# LED.net
KiCad netlist of a schematic drawn in Altium Designer
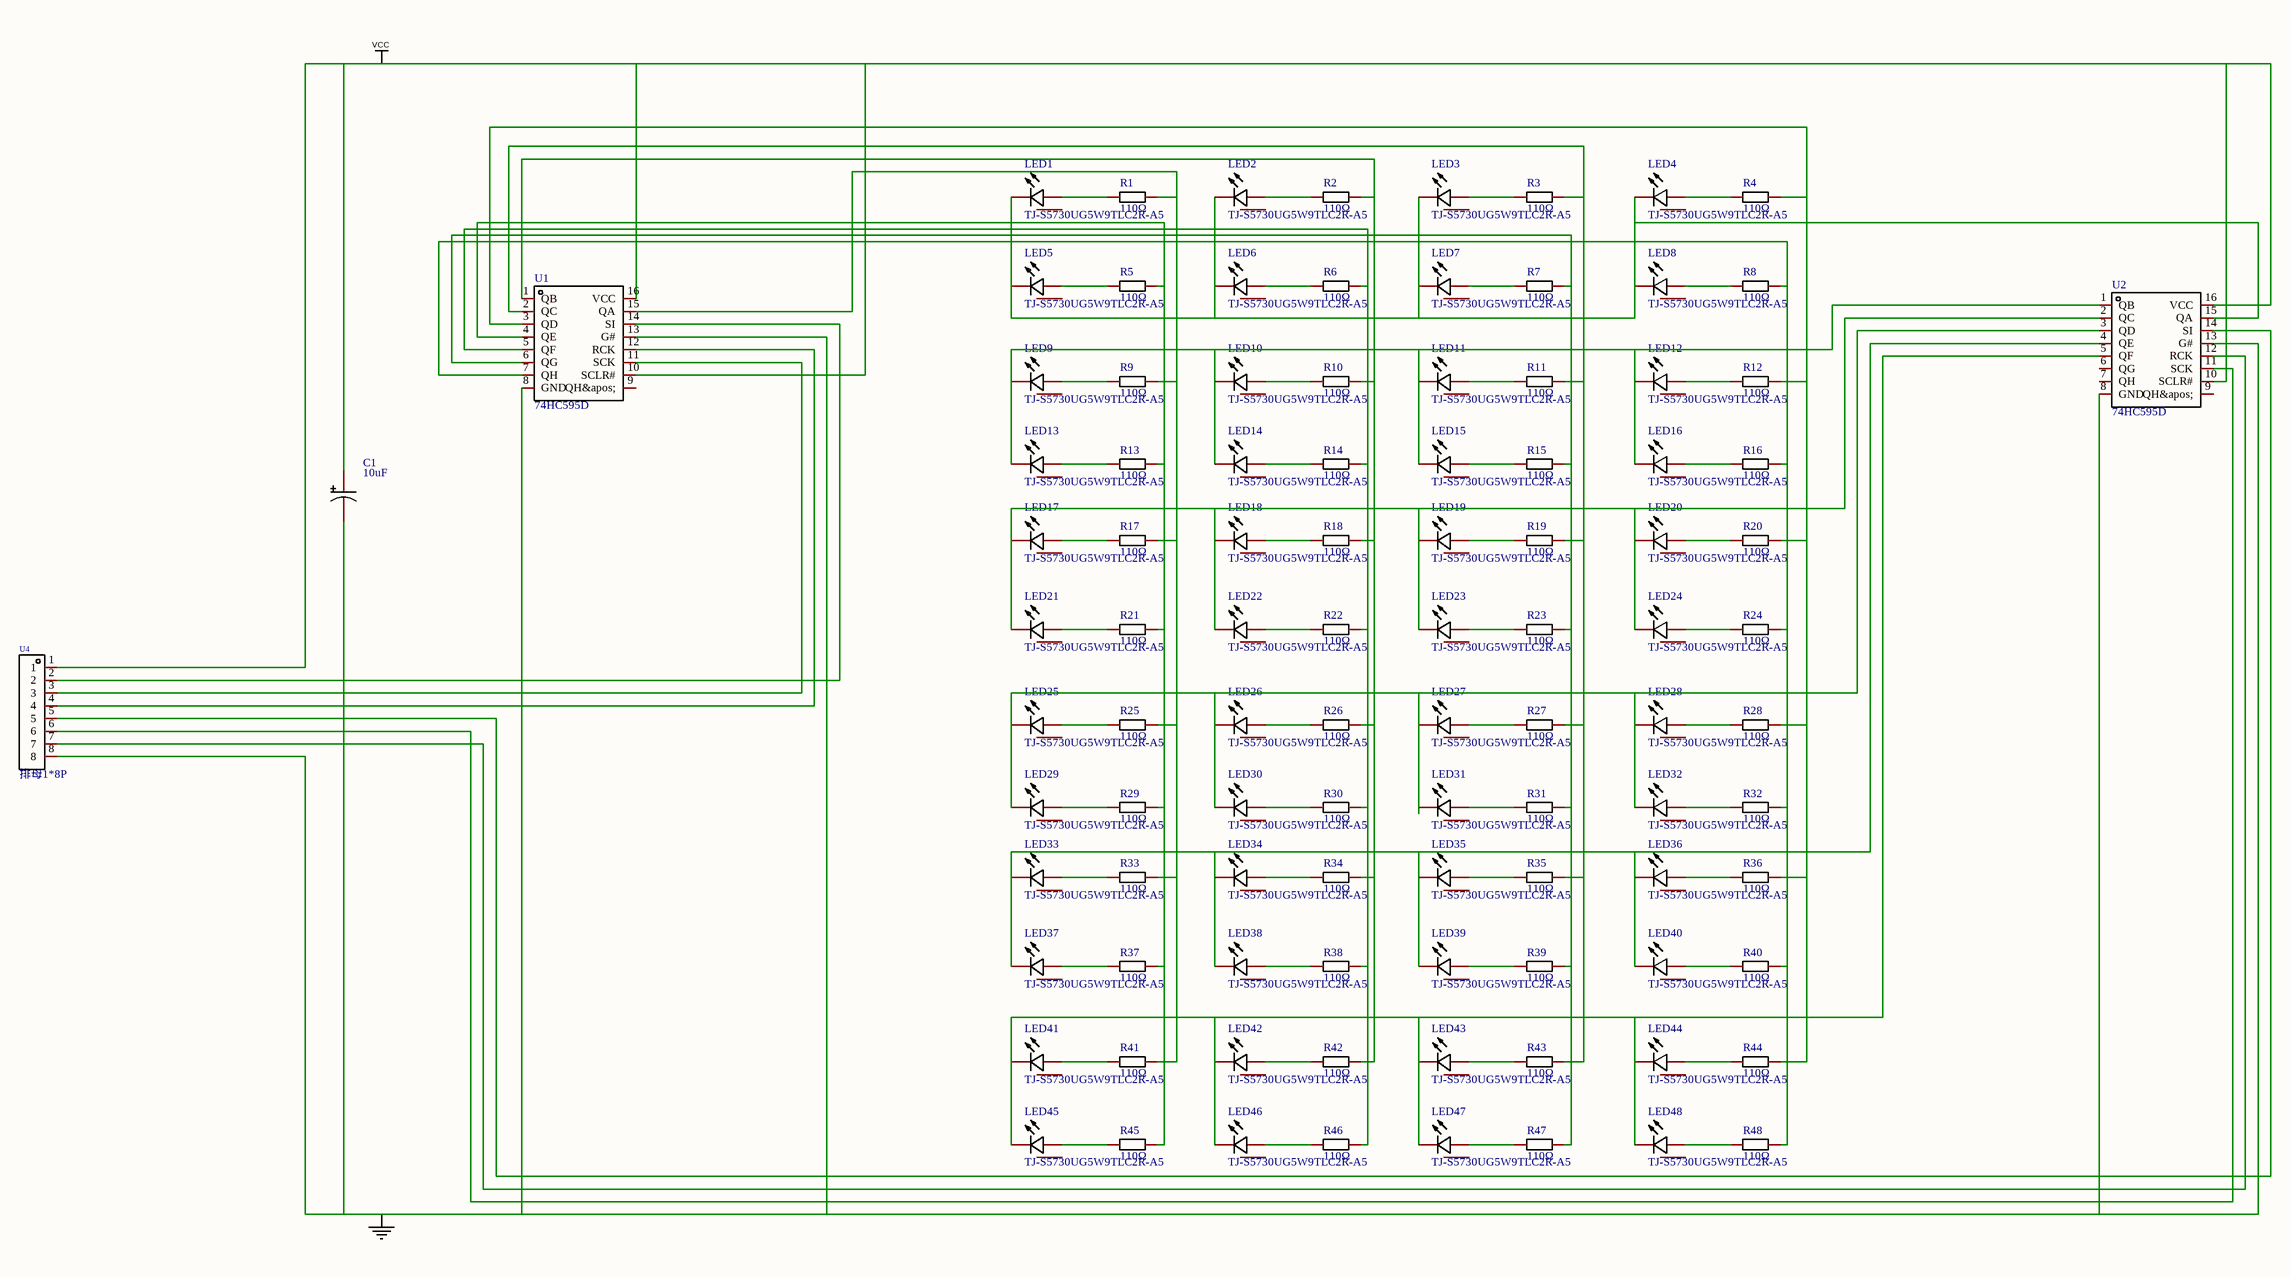
[diagram p0: LED.schdoc]

(export (version "E")
  (design (tool "Eeschema 10.0.6"))
  (components
    (comp (ref "C1")
      (value "10uF")
      (description "容值:10uF;精度:±20%;额定电压:50V;纹波电流:63.75mA@120Hz;等效串联电阻:-;")
      (fields
        (field (name "NAME") "10uF")
        (field (name "MANUFACTURER") "PANASONIC(松下)")
        (field (name "MANUFACTURER PART") "EEEFK1H100UR")
      )
      (libsource (lib "altium-import") (part "root_0_EEEFK1H100UR_"))
    )
    (comp (ref "LED1")
      (value "TJ-S5730UG5W9TLC2R-A5")
      (description "发光颜色:红灯;二极管配置:-;主波长:620nm~630nm;色温:-;功率:390mW;安装方式:-;")
      (fields (field (name "NAME") "TJ-S5730UG5W9TLC2R-A5") (field (name "MANUFACTURER") "TOGIALED(统佳)"))
      (libsource (lib "altium-import") (part "root_0_TJ-S5730UG5W9TLC2R-A5_"))
    )
    (comp (ref "LED2")
      (value "TJ-S5730UG5W9TLC2R-A5")
      (description "发光颜色:红灯;二极管配置:-;主波长:620nm~630nm;色温:-;功率:390mW;安装方式:-;")
      (fields (field (name "NAME") "TJ-S5730UG5W9TLC2R-A5") (field (name "MANUFACTURER") "TOGIALED(统佳)"))
      (libsource (lib "altium-import") (part "root_0_TJ-S5730UG5W9TLC2R-A5_"))
    )
    (comp (ref "LED3")
      (value "TJ-S5730UG5W9TLC2R-A5")
      (description "发光颜色:红灯;二极管配置:-;主波长:620nm~630nm;色温:-;功率:390mW;安装方式:-;")
      (fields (field (name "NAME") "TJ-S5730UG5W9TLC2R-A5") (field (name "MANUFACTURER") "TOGIALED(统佳)"))
      (libsource (lib "altium-import") (part "root_0_TJ-S5730UG5W9TLC2R-A5_"))
    )
    (comp (ref "LED4")
      (value "TJ-S5730UG5W9TLC2R-A5")
      (description "发光颜色:红灯;二极管配置:-;主波长:620nm~630nm;色温:-;功率:390mW;安装方式:-;")
      (fields (field (name "NAME") "TJ-S5730UG5W9TLC2R-A5") (field (name "MANUFACTURER") "TOGIALED(统佳)"))
      (libsource (lib "altium-import") (part "root_0_TJ-S5730UG5W9TLC2R-A5_"))
    )
    (comp (ref "LED5")
      (value "TJ-S5730UG5W9TLC2R-A5")
      (description "发光颜色:红灯;二极管配置:-;主波长:620nm~630nm;色温:-;功率:390mW;安装方式:-;")
      (fields (field (name "NAME") "TJ-S5730UG5W9TLC2R-A5") (field (name "MANUFACTURER") "TOGIALED(统佳)"))
      (libsource (lib "altium-import") (part "root_0_TJ-S5730UG5W9TLC2R-A5_"))
    )
    (comp (ref "LED6")
      (value "TJ-S5730UG5W9TLC2R-A5")
      (description "发光颜色:红灯;二极管配置:-;主波长:620nm~630nm;色温:-;功率:390mW;安装方式:-;")
      (fields (field (name "NAME") "TJ-S5730UG5W9TLC2R-A5") (field (name "MANUFACTURER") "TOGIALED(统佳)"))
      (libsource (lib "altium-import") (part "root_0_TJ-S5730UG5W9TLC2R-A5_"))
    )
    (comp (ref "LED7")
      (value "TJ-S5730UG5W9TLC2R-A5")
      (description "发光颜色:红灯;二极管配置:-;主波长:620nm~630nm;色温:-;功率:390mW;安装方式:-;")
      (fields (field (name "NAME") "TJ-S5730UG5W9TLC2R-A5") (field (name "MANUFACTURER") "TOGIALED(统佳)"))
      (libsource (lib "altium-import") (part "root_0_TJ-S5730UG5W9TLC2R-A5_"))
    )
    (comp (ref "LED8")
      (value "TJ-S5730UG5W9TLC2R-A5")
      (description "发光颜色:红灯;二极管配置:-;主波长:620nm~630nm;色温:-;功率:390mW;安装方式:-;")
      (fields (field (name "NAME") "TJ-S5730UG5W9TLC2R-A5") (field (name "MANUFACTURER") "TOGIALED(统佳)"))
      (libsource (lib "altium-import") (part "root_0_TJ-S5730UG5W9TLC2R-A5_"))
    )
    (comp (ref "LED9")
      (value "TJ-S5730UG5W9TLC2R-A5")
      (description "发光颜色:红灯;二极管配置:-;主波长:620nm~630nm;色温:-;功率:390mW;安装方式:-;")
      (fields (field (name "NAME") "TJ-S5730UG5W9TLC2R-A5") (field (name "MANUFACTURER") "TOGIALED(统佳)"))
      (libsource (lib "altium-import") (part "root_0_TJ-S5730UG5W9TLC2R-A5_"))
    )
    (comp (ref "LED10")
      (value "TJ-S5730UG5W9TLC2R-A5")
      (description "发光颜色:红灯;二极管配置:-;主波长:620nm~630nm;色温:-;功率:390mW;安装方式:-;")
      (fields (field (name "NAME") "TJ-S5730UG5W9TLC2R-A5") (field (name "MANUFACTURER") "TOGIALED(统佳)"))
      (libsource (lib "altium-import") (part "root_0_TJ-S5730UG5W9TLC2R-A5_"))
    )
    (comp (ref "LED11")
      (value "TJ-S5730UG5W9TLC2R-A5")
      (description "发光颜色:红灯;二极管配置:-;主波长:620nm~630nm;色温:-;功率:390mW;安装方式:-;")
      (fields (field (name "NAME") "TJ-S5730UG5W9TLC2R-A5") (field (name "MANUFACTURER") "TOGIALED(统佳)"))
      (libsource (lib "altium-import") (part "root_0_TJ-S5730UG5W9TLC2R-A5_"))
    )
    (comp (ref "LED12")
      (value "TJ-S5730UG5W9TLC2R-A5")
      (description "发光颜色:红灯;二极管配置:-;主波长:620nm~630nm;色温:-;功率:390mW;安装方式:-;")
      (fields (field (name "NAME") "TJ-S5730UG5W9TLC2R-A5") (field (name "MANUFACTURER") "TOGIALED(统佳)"))
      (libsource (lib "altium-import") (part "root_0_TJ-S5730UG5W9TLC2R-A5_"))
    )
    (comp (ref "LED13")
      (value "TJ-S5730UG5W9TLC2R-A5")
      (description "发光颜色:红灯;二极管配置:-;主波长:620nm~630nm;色温:-;功率:390mW;安装方式:-;")
      (fields (field (name "NAME") "TJ-S5730UG5W9TLC2R-A5") (field (name "MANUFACTURER") "TOGIALED(统佳)"))
      (libsource (lib "altium-import") (part "root_0_TJ-S5730UG5W9TLC2R-A5_"))
    )
    (comp (ref "LED14")
      (value "TJ-S5730UG5W9TLC2R-A5")
      (description "发光颜色:红灯;二极管配置:-;主波长:620nm~630nm;色温:-;功率:390mW;安装方式:-;")
      (fields (field (name "NAME") "TJ-S5730UG5W9TLC2R-A5") (field (name "MANUFACTURER") "TOGIALED(统佳)"))
      (libsource (lib "altium-import") (part "root_0_TJ-S5730UG5W9TLC2R-A5_"))
    )
    (comp (ref "LED15")
      (value "TJ-S5730UG5W9TLC2R-A5")
      (description "发光颜色:红灯;二极管配置:-;主波长:620nm~630nm;色温:-;功率:390mW;安装方式:-;")
      (fields (field (name "NAME") "TJ-S5730UG5W9TLC2R-A5") (field (name "MANUFACTURER") "TOGIALED(统佳)"))
      (libsource (lib "altium-import") (part "root_0_TJ-S5730UG5W9TLC2R-A5_"))
    )
    (comp (ref "LED16")
      (value "TJ-S5730UG5W9TLC2R-A5")
      (description "发光颜色:红灯;二极管配置:-;主波长:620nm~630nm;色温:-;功率:390mW;安装方式:-;")
      (fields (field (name "NAME") "TJ-S5730UG5W9TLC2R-A5") (field (name "MANUFACTURER") "TOGIALED(统佳)"))
      (libsource (lib "altium-import") (part "root_0_TJ-S5730UG5W9TLC2R-A5_"))
    )
    (comp (ref "LED17")
      (value "TJ-S5730UG5W9TLC2R-A5")
      (description "发光颜色:红灯;二极管配置:-;主波长:620nm~630nm;色温:-;功率:390mW;安装方式:-;")
      (fields (field (name "NAME") "TJ-S5730UG5W9TLC2R-A5") (field (name "MANUFACTURER") "TOGIALED(统佳)"))
      (libsource (lib "altium-import") (part "root_0_TJ-S5730UG5W9TLC2R-A5_"))
    )
    (comp (ref "LED18")
      (value "TJ-S5730UG5W9TLC2R-A5")
      (description "发光颜色:红灯;二极管配置:-;主波长:620nm~630nm;色温:-;功率:390mW;安装方式:-;")
      (fields (field (name "NAME") "TJ-S5730UG5W9TLC2R-A5") (field (name "MANUFACTURER") "TOGIALED(统佳)"))
      (libsource (lib "altium-import") (part "root_0_TJ-S5730UG5W9TLC2R-A5_"))
    )
    (comp (ref "LED19")
      (value "TJ-S5730UG5W9TLC2R-A5")
      (description "发光颜色:红灯;二极管配置:-;主波长:620nm~630nm;色温:-;功率:390mW;安装方式:-;")
      (fields (field (name "NAME") "TJ-S5730UG5W9TLC2R-A5") (field (name "MANUFACTURER") "TOGIALED(统佳)"))
      (libsource (lib "altium-import") (part "root_0_TJ-S5730UG5W9TLC2R-A5_"))
    )
    (comp (ref "LED20")
      (value "TJ-S5730UG5W9TLC2R-A5")
      (description "发光颜色:红灯;二极管配置:-;主波长:620nm~630nm;色温:-;功率:390mW;安装方式:-;")
      (fields (field (name "NAME") "TJ-S5730UG5W9TLC2R-A5") (field (name "MANUFACTURER") "TOGIALED(统佳)"))
      (libsource (lib "altium-import") (part "root_0_TJ-S5730UG5W9TLC2R-A5_"))
    )
    (comp (ref "LED21")
      (value "TJ-S5730UG5W9TLC2R-A5")
      (description "发光颜色:红灯;二极管配置:-;主波长:620nm~630nm;色温:-;功率:390mW;安装方式:-;")
      (fields (field (name "NAME") "TJ-S5730UG5W9TLC2R-A5") (field (name "MANUFACTURER") "TOGIALED(统佳)"))
      (libsource (lib "altium-import") (part "root_0_TJ-S5730UG5W9TLC2R-A5_"))
    )
    (comp (ref "LED22")
      (value "TJ-S5730UG5W9TLC2R-A5")
      (description "发光颜色:红灯;二极管配置:-;主波长:620nm~630nm;色温:-;功率:390mW;安装方式:-;")
      (fields (field (name "NAME") "TJ-S5730UG5W9TLC2R-A5") (field (name "MANUFACTURER") "TOGIALED(统佳)"))
      (libsource (lib "altium-import") (part "root_0_TJ-S5730UG5W9TLC2R-A5_"))
    )
    (comp (ref "LED23")
      (value "TJ-S5730UG5W9TLC2R-A5")
      (description "发光颜色:红灯;二极管配置:-;主波长:620nm~630nm;色温:-;功率:390mW;安装方式:-;")
      (fields (field (name "NAME") "TJ-S5730UG5W9TLC2R-A5") (field (name "MANUFACTURER") "TOGIALED(统佳)"))
      (libsource (lib "altium-import") (part "root_0_TJ-S5730UG5W9TLC2R-A5_"))
    )
    (comp (ref "LED24")
      (value "TJ-S5730UG5W9TLC2R-A5")
      (description "发光颜色:红灯;二极管配置:-;主波长:620nm~630nm;色温:-;功率:390mW;安装方式:-;")
      (fields (field (name "NAME") "TJ-S5730UG5W9TLC2R-A5") (field (name "MANUFACTURER") "TOGIALED(统佳)"))
      (libsource (lib "altium-import") (part "root_0_TJ-S5730UG5W9TLC2R-A5_"))
    )
    (comp (ref "LED25")
      (value "TJ-S5730UG5W9TLC2R-A5")
      (description "发光颜色:红灯;二极管配置:-;主波长:620nm~630nm;色温:-;功率:390mW;安装方式:-;")
      (fields (field (name "NAME") "TJ-S5730UG5W9TLC2R-A5") (field (name "MANUFACTURER") "TOGIALED(统佳)"))
      (libsource (lib "altium-import") (part "root_0_TJ-S5730UG5W9TLC2R-A5_"))
    )
    (comp (ref "LED26")
      (value "TJ-S5730UG5W9TLC2R-A5")
      (description "发光颜色:红灯;二极管配置:-;主波长:620nm~630nm;色温:-;功率:390mW;安装方式:-;")
      (fields (field (name "NAME") "TJ-S5730UG5W9TLC2R-A5") (field (name "MANUFACTURER") "TOGIALED(统佳)"))
      (libsource (lib "altium-import") (part "root_0_TJ-S5730UG5W9TLC2R-A5_"))
    )
    (comp (ref "LED27")
      (value "TJ-S5730UG5W9TLC2R-A5")
      (description "发光颜色:红灯;二极管配置:-;主波长:620nm~630nm;色温:-;功率:390mW;安装方式:-;")
      (fields (field (name "NAME") "TJ-S5730UG5W9TLC2R-A5") (field (name "MANUFACTURER") "TOGIALED(统佳)"))
      (libsource (lib "altium-import") (part "root_0_TJ-S5730UG5W9TLC2R-A5_"))
    )
    (comp (ref "LED28")
      (value "TJ-S5730UG5W9TLC2R-A5")
      (description "发光颜色:红灯;二极管配置:-;主波长:620nm~630nm;色温:-;功率:390mW;安装方式:-;")
      (fields (field (name "NAME") "TJ-S5730UG5W9TLC2R-A5") (field (name "MANUFACTURER") "TOGIALED(统佳)"))
      (libsource (lib "altium-import") (part "root_0_TJ-S5730UG5W9TLC2R-A5_"))
    )
    (comp (ref "LED29")
      (value "TJ-S5730UG5W9TLC2R-A5")
      (description "发光颜色:红灯;二极管配置:-;主波长:620nm~630nm;色温:-;功率:390mW;安装方式:-;")
      (fields (field (name "NAME") "TJ-S5730UG5W9TLC2R-A5") (field (name "MANUFACTURER") "TOGIALED(统佳)"))
      (libsource (lib "altium-import") (part "root_0_TJ-S5730UG5W9TLC2R-A5_"))
    )
    (comp (ref "LED30")
      (value "TJ-S5730UG5W9TLC2R-A5")
      (description "发光颜色:红灯;二极管配置:-;主波长:620nm~630nm;色温:-;功率:390mW;安装方式:-;")
      (fields (field (name "NAME") "TJ-S5730UG5W9TLC2R-A5") (field (name "MANUFACTURER") "TOGIALED(统佳)"))
      (libsource (lib "altium-import") (part "root_0_TJ-S5730UG5W9TLC2R-A5_"))
    )
    (comp (ref "LED31")
      (value "TJ-S5730UG5W9TLC2R-A5")
      (description "发光颜色:红灯;二极管配置:-;主波长:620nm~630nm;色温:-;功率:390mW;安装方式:-;")
      (fields (field (name "NAME") "TJ-S5730UG5W9TLC2R-A5") (field (name "MANUFACTURER") "TOGIALED(统佳)"))
      (libsource (lib "altium-import") (part "root_0_TJ-S5730UG5W9TLC2R-A5_"))
    )
    (comp (ref "LED32")
      (value "TJ-S5730UG5W9TLC2R-A5")
      (description "发光颜色:红灯;二极管配置:-;主波长:620nm~630nm;色温:-;功率:390mW;安装方式:-;")
      (fields (field (name "NAME") "TJ-S5730UG5W9TLC2R-A5") (field (name "MANUFACTURER") "TOGIALED(统佳)"))
      (libsource (lib "altium-import") (part "root_0_TJ-S5730UG5W9TLC2R-A5_"))
    )
    (comp (ref "LED33")
      (value "TJ-S5730UG5W9TLC2R-A5")
      (description "发光颜色:红灯;二极管配置:-;主波长:620nm~630nm;色温:-;功率:390mW;安装方式:-;")
      (fields (field (name "NAME") "TJ-S5730UG5W9TLC2R-A5") (field (name "MANUFACTURER") "TOGIALED(统佳)"))
      (libsource (lib "altium-import") (part "root_0_TJ-S5730UG5W9TLC2R-A5_"))
    )
    (comp (ref "LED34")
      (value "TJ-S5730UG5W9TLC2R-A5")
      (description "发光颜色:红灯;二极管配置:-;主波长:620nm~630nm;色温:-;功率:390mW;安装方式:-;")
      (fields (field (name "NAME") "TJ-S5730UG5W9TLC2R-A5") (field (name "MANUFACTURER") "TOGIALED(统佳)"))
      (libsource (lib "altium-import") (part "root_0_TJ-S5730UG5W9TLC2R-A5_"))
    )
    (comp (ref "LED35")
      (value "TJ-S5730UG5W9TLC2R-A5")
      (description "发光颜色:红灯;二极管配置:-;主波长:620nm~630nm;色温:-;功率:390mW;安装方式:-;")
      (fields (field (name "NAME") "TJ-S5730UG5W9TLC2R-A5") (field (name "MANUFACTURER") "TOGIALED(统佳)"))
      (libsource (lib "altium-import") (part "root_0_TJ-S5730UG5W9TLC2R-A5_"))
    )
    (comp (ref "LED36")
      (value "TJ-S5730UG5W9TLC2R-A5")
      (description "发光颜色:红灯;二极管配置:-;主波长:620nm~630nm;色温:-;功率:390mW;安装方式:-;")
      (fields (field (name "NAME") "TJ-S5730UG5W9TLC2R-A5") (field (name "MANUFACTURER") "TOGIALED(统佳)"))
      (libsource (lib "altium-import") (part "root_0_TJ-S5730UG5W9TLC2R-A5_"))
    )
    (comp (ref "LED37")
      (value "TJ-S5730UG5W9TLC2R-A5")
      (description "发光颜色:红灯;二极管配置:-;主波长:620nm~630nm;色温:-;功率:390mW;安装方式:-;")
      (fields (field (name "NAME") "TJ-S5730UG5W9TLC2R-A5") (field (name "MANUFACTURER") "TOGIALED(统佳)"))
      (libsource (lib "altium-import") (part "root_0_TJ-S5730UG5W9TLC2R-A5_"))
    )
    (comp (ref "LED38")
      (value "TJ-S5730UG5W9TLC2R-A5")
      (description "发光颜色:红灯;二极管配置:-;主波长:620nm~630nm;色温:-;功率:390mW;安装方式:-;")
      (fields (field (name "NAME") "TJ-S5730UG5W9TLC2R-A5") (field (name "MANUFACTURER") "TOGIALED(统佳)"))
      (libsource (lib "altium-import") (part "root_0_TJ-S5730UG5W9TLC2R-A5_"))
    )
    (comp (ref "LED39")
      (value "TJ-S5730UG5W9TLC2R-A5")
      (description "发光颜色:红灯;二极管配置:-;主波长:620nm~630nm;色温:-;功率:390mW;安装方式:-;")
      (fields (field (name "NAME") "TJ-S5730UG5W9TLC2R-A5") (field (name "MANUFACTURER") "TOGIALED(统佳)"))
      (libsource (lib "altium-import") (part "root_0_TJ-S5730UG5W9TLC2R-A5_"))
    )
    (comp (ref "LED40")
      (value "TJ-S5730UG5W9TLC2R-A5")
      (description "发光颜色:红灯;二极管配置:-;主波长:620nm~630nm;色温:-;功率:390mW;安装方式:-;")
      (fields (field (name "NAME") "TJ-S5730UG5W9TLC2R-A5") (field (name "MANUFACTURER") "TOGIALED(统佳)"))
      (libsource (lib "altium-import") (part "root_0_TJ-S5730UG5W9TLC2R-A5_"))
    )
    (comp (ref "LED41")
      (value "TJ-S5730UG5W9TLC2R-A5")
      (description "发光颜色:红灯;二极管配置:-;主波长:620nm~630nm;色温:-;功率:390mW;安装方式:-;")
      (fields (field (name "NAME") "TJ-S5730UG5W9TLC2R-A5") (field (name "MANUFACTURER") "TOGIALED(统佳)"))
      (libsource (lib "altium-import") (part "root_0_TJ-S5730UG5W9TLC2R-A5_"))
    )
    (comp (ref "LED42")
      (value "TJ-S5730UG5W9TLC2R-A5")
      (description "发光颜色:红灯;二极管配置:-;主波长:620nm~630nm;色温:-;功率:390mW;安装方式:-;")
      (fields (field (name "NAME") "TJ-S5730UG5W9TLC2R-A5") (field (name "MANUFACTURER") "TOGIALED(统佳)"))
      (libsource (lib "altium-import") (part "root_0_TJ-S5730UG5W9TLC2R-A5_"))
    )
    (comp (ref "LED43")
      (value "TJ-S5730UG5W9TLC2R-A5")
      (description "发光颜色:红灯;二极管配置:-;主波长:620nm~630nm;色温:-;功率:390mW;安装方式:-;")
      (fields (field (name "NAME") "TJ-S5730UG5W9TLC2R-A5") (field (name "MANUFACTURER") "TOGIALED(统佳)"))
      (libsource (lib "altium-import") (part "root_0_TJ-S5730UG5W9TLC2R-A5_"))
    )
    (comp (ref "LED44")
      (value "TJ-S5730UG5W9TLC2R-A5")
      (description "发光颜色:红灯;二极管配置:-;主波长:620nm~630nm;色温:-;功率:390mW;安装方式:-;")
      (fields (field (name "NAME") "TJ-S5730UG5W9TLC2R-A5") (field (name "MANUFACTURER") "TOGIALED(统佳)"))
      (libsource (lib "altium-import") (part "root_0_TJ-S5730UG5W9TLC2R-A5_"))
    )
    (comp (ref "LED45")
      (value "TJ-S5730UG5W9TLC2R-A5")
      (description "发光颜色:红灯;二极管配置:-;主波长:620nm~630nm;色温:-;功率:390mW;安装方式:-;")
      (fields (field (name "NAME") "TJ-S5730UG5W9TLC2R-A5") (field (name "MANUFACTURER") "TOGIALED(统佳)"))
      (libsource (lib "altium-import") (part "root_0_TJ-S5730UG5W9TLC2R-A5_"))
    )
    (comp (ref "LED46")
      (value "TJ-S5730UG5W9TLC2R-A5")
      (description "发光颜色:红灯;二极管配置:-;主波长:620nm~630nm;色温:-;功率:390mW;安装方式:-;")
      (fields (field (name "NAME") "TJ-S5730UG5W9TLC2R-A5") (field (name "MANUFACTURER") "TOGIALED(统佳)"))
      (libsource (lib "altium-import") (part "root_0_TJ-S5730UG5W9TLC2R-A5_"))
    )
    (comp (ref "LED47")
      (value "TJ-S5730UG5W9TLC2R-A5")
      (description "发光颜色:红灯;二极管配置:-;主波长:620nm~630nm;色温:-;功率:390mW;安装方式:-;")
      (fields (field (name "NAME") "TJ-S5730UG5W9TLC2R-A5") (field (name "MANUFACTURER") "TOGIALED(统佳)"))
      (libsource (lib "altium-import") (part "root_0_TJ-S5730UG5W9TLC2R-A5_"))
    )
    (comp (ref "LED48")
      (value "TJ-S5730UG5W9TLC2R-A5")
      (description "发光颜色:红灯;二极管配置:-;主波长:620nm~630nm;色温:-;功率:390mW;安装方式:-;")
      (fields (field (name "NAME") "TJ-S5730UG5W9TLC2R-A5") (field (name "MANUFACTURER") "TOGIALED(统佳)"))
      (libsource (lib "altium-import") (part "root_0_TJ-S5730UG5W9TLC2R-A5_"))
    )
    (comp (ref "R1")
      (value "110Ω")
      (description "电阻类型:厚膜电阻;阻值:110Ω;精度:±1%;功率:100mW;")
      (fields
        (field (name "NAME") "110Ω")
        (field (name "MANUFACTURER") "UNI-ROYAL(厚声)")
        (field (name "MANUFACTURER PART") "0603WAF1100T5E")
      )
      (libsource (lib "altium-import") (part "root_0_0603WAF1100T5E_"))
    )
    (comp (ref "R2")
      (value "110Ω")
      (description "电阻类型:厚膜电阻;阻值:110Ω;精度:±1%;功率:100mW;")
      (fields
        (field (name "NAME") "110Ω")
        (field (name "MANUFACTURER") "UNI-ROYAL(厚声)")
        (field (name "MANUFACTURER PART") "0603WAF1100T5E")
      )
      (libsource (lib "altium-import") (part "root_0_0603WAF1100T5E_"))
    )
    (comp (ref "R3")
      (value "110Ω")
      (description "电阻类型:厚膜电阻;阻值:110Ω;精度:±1%;功率:100mW;")
      (fields
        (field (name "NAME") "110Ω")
        (field (name "MANUFACTURER") "UNI-ROYAL(厚声)")
        (field (name "MANUFACTURER PART") "0603WAF1100T5E")
      )
      (libsource (lib "altium-import") (part "root_0_0603WAF1100T5E_"))
    )
    (comp (ref "R4")
      (value "110Ω")
      (description "电阻类型:厚膜电阻;阻值:110Ω;精度:±1%;功率:100mW;")
      (fields
        (field (name "NAME") "110Ω")
        (field (name "MANUFACTURER") "UNI-ROYAL(厚声)")
        (field (name "MANUFACTURER PART") "0603WAF1100T5E")
      )
      (libsource (lib "altium-import") (part "root_0_0603WAF1100T5E_"))
    )
    (comp (ref "R5")
      (value "110Ω")
      (description "电阻类型:厚膜电阻;阻值:110Ω;精度:±1%;功率:100mW;")
      (fields
        (field (name "NAME") "110Ω")
        (field (name "MANUFACTURER") "UNI-ROYAL(厚声)")
        (field (name "MANUFACTURER PART") "0603WAF1100T5E")
      )
      (libsource (lib "altium-import") (part "root_0_0603WAF1100T5E_"))
    )
    (comp (ref "R6")
      (value "110Ω")
      (description "电阻类型:厚膜电阻;阻值:110Ω;精度:±1%;功率:100mW;")
      (fields
        (field (name "NAME") "110Ω")
        (field (name "MANUFACTURER") "UNI-ROYAL(厚声)")
        (field (name "MANUFACTURER PART") "0603WAF1100T5E")
      )
      (libsource (lib "altium-import") (part "root_0_0603WAF1100T5E_"))
    )
    (comp (ref "R7")
      (value "110Ω")
      (description "电阻类型:厚膜电阻;阻值:110Ω;精度:±1%;功率:100mW;")
      (fields
        (field (name "NAME") "110Ω")
        (field (name "MANUFACTURER") "UNI-ROYAL(厚声)")
        (field (name "MANUFACTURER PART") "0603WAF1100T5E")
      )
      (libsource (lib "altium-import") (part "root_0_0603WAF1100T5E_"))
    )
    (comp (ref "R8")
      (value "110Ω")
      (description "电阻类型:厚膜电阻;阻值:110Ω;精度:±1%;功率:100mW;")
      (fields
        (field (name "NAME") "110Ω")
        (field (name "MANUFACTURER") "UNI-ROYAL(厚声)")
        (field (name "MANUFACTURER PART") "0603WAF1100T5E")
      )
      (libsource (lib "altium-import") (part "root_0_0603WAF1100T5E_"))
    )
    (comp (ref "R9")
      (value "110Ω")
      (description "电阻类型:厚膜电阻;阻值:110Ω;精度:±1%;功率:100mW;")
      (fields
        (field (name "NAME") "110Ω")
        (field (name "MANUFACTURER") "UNI-ROYAL(厚声)")
        (field (name "MANUFACTURER PART") "0603WAF1100T5E")
      )
      (libsource (lib "altium-import") (part "root_0_0603WAF1100T5E_"))
    )
    (comp (ref "R10")
      (value "110Ω")
      (description "电阻类型:厚膜电阻;阻值:110Ω;精度:±1%;功率:100mW;")
      (fields
        (field (name "NAME") "110Ω")
        (field (name "MANUFACTURER") "UNI-ROYAL(厚声)")
        (field (name "MANUFACTURER PART") "0603WAF1100T5E")
      )
      (libsource (lib "altium-import") (part "root_0_0603WAF1100T5E_"))
    )
    (comp (ref "R11")
      (value "110Ω")
      (description "电阻类型:厚膜电阻;阻值:110Ω;精度:±1%;功率:100mW;")
      (fields
        (field (name "NAME") "110Ω")
        (field (name "MANUFACTURER") "UNI-ROYAL(厚声)")
        (field (name "MANUFACTURER PART") "0603WAF1100T5E")
      )
      (libsource (lib "altium-import") (part "root_0_0603WAF1100T5E_"))
    )
    (comp (ref "R12")
      (value "110Ω")
      (description "电阻类型:厚膜电阻;阻值:110Ω;精度:±1%;功率:100mW;")
      (fields
        (field (name "NAME") "110Ω")
        (field (name "MANUFACTURER") "UNI-ROYAL(厚声)")
        (field (name "MANUFACTURER PART") "0603WAF1100T5E")
      )
      (libsource (lib "altium-import") (part "root_0_0603WAF1100T5E_"))
    )
    (comp (ref "R13")
      (value "110Ω")
      (description "电阻类型:厚膜电阻;阻值:110Ω;精度:±1%;功率:100mW;")
      (fields
        (field (name "NAME") "110Ω")
        (field (name "MANUFACTURER") "UNI-ROYAL(厚声)")
        (field (name "MANUFACTURER PART") "0603WAF1100T5E")
      )
      (libsource (lib "altium-import") (part "root_0_0603WAF1100T5E_"))
    )
    (comp (ref "R14")
      (value "110Ω")
      (description "电阻类型:厚膜电阻;阻值:110Ω;精度:±1%;功率:100mW;")
      (fields
        (field (name "NAME") "110Ω")
        (field (name "MANUFACTURER") "UNI-ROYAL(厚声)")
        (field (name "MANUFACTURER PART") "0603WAF1100T5E")
      )
      (libsource (lib "altium-import") (part "root_0_0603WAF1100T5E_"))
    )
    (comp (ref "R15")
      (value "110Ω")
      (description "电阻类型:厚膜电阻;阻值:110Ω;精度:±1%;功率:100mW;")
      (fields
        (field (name "NAME") "110Ω")
        (field (name "MANUFACTURER") "UNI-ROYAL(厚声)")
        (field (name "MANUFACTURER PART") "0603WAF1100T5E")
      )
      (libsource (lib "altium-import") (part "root_0_0603WAF1100T5E_"))
    )
    (comp (ref "R16")
      (value "110Ω")
      (description "电阻类型:厚膜电阻;阻值:110Ω;精度:±1%;功率:100mW;")
      (fields
        (field (name "NAME") "110Ω")
        (field (name "MANUFACTURER") "UNI-ROYAL(厚声)")
        (field (name "MANUFACTURER PART") "0603WAF1100T5E")
      )
      (libsource (lib "altium-import") (part "root_0_0603WAF1100T5E_"))
    )
    (comp (ref "R17")
      (value "110Ω")
      (description "电阻类型:厚膜电阻;阻值:110Ω;精度:±1%;功率:100mW;")
      (fields
        (field (name "NAME") "110Ω")
        (field (name "MANUFACTURER") "UNI-ROYAL(厚声)")
        (field (name "MANUFACTURER PART") "0603WAF1100T5E")
      )
      (libsource (lib "altium-import") (part "root_0_0603WAF1100T5E_"))
    )
    (comp (ref "R18")
      (value "110Ω")
      (description "电阻类型:厚膜电阻;阻值:110Ω;精度:±1%;功率:100mW;")
      (fields
        (field (name "NAME") "110Ω")
        (field (name "MANUFACTURER") "UNI-ROYAL(厚声)")
        (field (name "MANUFACTURER PART") "0603WAF1100T5E")
      )
      (libsource (lib "altium-import") (part "root_0_0603WAF1100T5E_"))
    )
    (comp (ref "R19")
      (value "110Ω")
      (description "电阻类型:厚膜电阻;阻值:110Ω;精度:±1%;功率:100mW;")
      (fields
        (field (name "NAME") "110Ω")
        (field (name "MANUFACTURER") "UNI-ROYAL(厚声)")
        (field (name "MANUFACTURER PART") "0603WAF1100T5E")
      )
      (libsource (lib "altium-import") (part "root_0_0603WAF1100T5E_"))
    )
    (comp (ref "R20")
      (value "110Ω")
      (description "电阻类型:厚膜电阻;阻值:110Ω;精度:±1%;功率:100mW;")
      (fields
        (field (name "NAME") "110Ω")
        (field (name "MANUFACTURER") "UNI-ROYAL(厚声)")
        (field (name "MANUFACTURER PART") "0603WAF1100T5E")
      )
      (libsource (lib "altium-import") (part "root_0_0603WAF1100T5E_"))
    )
    (comp (ref "R21")
      (value "110Ω")
      (description "电阻类型:厚膜电阻;阻值:110Ω;精度:±1%;功率:100mW;")
      (fields
        (field (name "NAME") "110Ω")
        (field (name "MANUFACTURER") "UNI-ROYAL(厚声)")
        (field (name "MANUFACTURER PART") "0603WAF1100T5E")
      )
      (libsource (lib "altium-import") (part "root_0_0603WAF1100T5E_"))
    )
    (comp (ref "R22")
      (value "110Ω")
      (description "电阻类型:厚膜电阻;阻值:110Ω;精度:±1%;功率:100mW;")
      (fields
        (field (name "NAME") "110Ω")
        (field (name "MANUFACTURER") "UNI-ROYAL(厚声)")
        (field (name "MANUFACTURER PART") "0603WAF1100T5E")
      )
      (libsource (lib "altium-import") (part "root_0_0603WAF1100T5E_"))
    )
    (comp (ref "R23")
      (value "110Ω")
      (description "电阻类型:厚膜电阻;阻值:110Ω;精度:±1%;功率:100mW;")
      (fields
        (field (name "NAME") "110Ω")
        (field (name "MANUFACTURER") "UNI-ROYAL(厚声)")
        (field (name "MANUFACTURER PART") "0603WAF1100T5E")
      )
      (libsource (lib "altium-import") (part "root_0_0603WAF1100T5E_"))
    )
    (comp (ref "R24")
      (value "110Ω")
      (description "电阻类型:厚膜电阻;阻值:110Ω;精度:±1%;功率:100mW;")
      (fields
        (field (name "NAME") "110Ω")
        (field (name "MANUFACTURER") "UNI-ROYAL(厚声)")
        (field (name "MANUFACTURER PART") "0603WAF1100T5E")
      )
      (libsource (lib "altium-import") (part "root_0_0603WAF1100T5E_"))
    )
    (comp (ref "R25")
      (value "110Ω")
      (description "电阻类型:厚膜电阻;阻值:110Ω;精度:±1%;功率:100mW;")
      (fields
        (field (name "NAME") "110Ω")
        (field (name "MANUFACTURER") "UNI-ROYAL(厚声)")
        (field (name "MANUFACTURER PART") "0603WAF1100T5E")
      )
      (libsource (lib "altium-import") (part "root_0_0603WAF1100T5E_"))
    )
    (comp (ref "R26")
      (value "110Ω")
      (description "电阻类型:厚膜电阻;阻值:110Ω;精度:±1%;功率:100mW;")
      (fields
        (field (name "NAME") "110Ω")
        (field (name "MANUFACTURER") "UNI-ROYAL(厚声)")
        (field (name "MANUFACTURER PART") "0603WAF1100T5E")
      )
      (libsource (lib "altium-import") (part "root_0_0603WAF1100T5E_"))
    )
    (comp (ref "R27")
      (value "110Ω")
      (description "电阻类型:厚膜电阻;阻值:110Ω;精度:±1%;功率:100mW;")
      (fields
        (field (name "NAME") "110Ω")
        (field (name "MANUFACTURER") "UNI-ROYAL(厚声)")
        (field (name "MANUFACTURER PART") "0603WAF1100T5E")
      )
      (libsource (lib "altium-import") (part "root_0_0603WAF1100T5E_"))
    )
    (comp (ref "R28")
      (value "110Ω")
      (description "电阻类型:厚膜电阻;阻值:110Ω;精度:±1%;功率:100mW;")
      (fields
        (field (name "NAME") "110Ω")
        (field (name "MANUFACTURER") "UNI-ROYAL(厚声)")
        (field (name "MANUFACTURER PART") "0603WAF1100T5E")
      )
      (libsource (lib "altium-import") (part "root_0_0603WAF1100T5E_"))
    )
    (comp (ref "R29")
      (value "110Ω")
      (description "电阻类型:厚膜电阻;阻值:110Ω;精度:±1%;功率:100mW;")
      (fields
        (field (name "NAME") "110Ω")
        (field (name "MANUFACTURER") "UNI-ROYAL(厚声)")
        (field (name "MANUFACTURER PART") "0603WAF1100T5E")
      )
      (libsource (lib "altium-import") (part "root_0_0603WAF1100T5E_"))
    )
    (comp (ref "R30")
      (value "110Ω")
      (description "电阻类型:厚膜电阻;阻值:110Ω;精度:±1%;功率:100mW;")
      (fields
        (field (name "NAME") "110Ω")
        (field (name "MANUFACTURER") "UNI-ROYAL(厚声)")
        (field (name "MANUFACTURER PART") "0603WAF1100T5E")
      )
      (libsource (lib "altium-import") (part "root_0_0603WAF1100T5E_"))
    )
    (comp (ref "R31")
      (value "110Ω")
      (description "电阻类型:厚膜电阻;阻值:110Ω;精度:±1%;功率:100mW;")
      (fields
        (field (name "NAME") "110Ω")
        (field (name "MANUFACTURER") "UNI-ROYAL(厚声)")
        (field (name "MANUFACTURER PART") "0603WAF1100T5E")
      )
      (libsource (lib "altium-import") (part "root_0_0603WAF1100T5E_"))
    )
    (comp (ref "R32")
      (value "110Ω")
      (description "电阻类型:厚膜电阻;阻值:110Ω;精度:±1%;功率:100mW;")
      (fields
        (field (name "NAME") "110Ω")
        (field (name "MANUFACTURER") "UNI-ROYAL(厚声)")
        (field (name "MANUFACTURER PART") "0603WAF1100T5E")
      )
      (libsource (lib "altium-import") (part "root_0_0603WAF1100T5E_"))
    )
    (comp (ref "R33")
      (value "110Ω")
      (description "电阻类型:厚膜电阻;阻值:110Ω;精度:±1%;功率:100mW;")
      (fields
        (field (name "NAME") "110Ω")
        (field (name "MANUFACTURER") "UNI-ROYAL(厚声)")
        (field (name "MANUFACTURER PART") "0603WAF1100T5E")
      )
      (libsource (lib "altium-import") (part "root_0_0603WAF1100T5E_"))
    )
    (comp (ref "R34")
      (value "110Ω")
      (description "电阻类型:厚膜电阻;阻值:110Ω;精度:±1%;功率:100mW;")
      (fields
        (field (name "NAME") "110Ω")
        (field (name "MANUFACTURER") "UNI-ROYAL(厚声)")
        (field (name "MANUFACTURER PART") "0603WAF1100T5E")
      )
      (libsource (lib "altium-import") (part "root_0_0603WAF1100T5E_"))
    )
    (comp (ref "R35")
      (value "110Ω")
      (description "电阻类型:厚膜电阻;阻值:110Ω;精度:±1%;功率:100mW;")
      (fields
        (field (name "NAME") "110Ω")
        (field (name "MANUFACTURER") "UNI-ROYAL(厚声)")
        (field (name "MANUFACTURER PART") "0603WAF1100T5E")
      )
      (libsource (lib "altium-import") (part "root_0_0603WAF1100T5E_"))
    )
    (comp (ref "R36")
      (value "110Ω")
      (description "电阻类型:厚膜电阻;阻值:110Ω;精度:±1%;功率:100mW;")
      (fields
        (field (name "NAME") "110Ω")
        (field (name "MANUFACTURER") "UNI-ROYAL(厚声)")
        (field (name "MANUFACTURER PART") "0603WAF1100T5E")
      )
      (libsource (lib "altium-import") (part "root_0_0603WAF1100T5E_"))
    )
    (comp (ref "R37")
      (value "110Ω")
      (description "电阻类型:厚膜电阻;阻值:110Ω;精度:±1%;功率:100mW;")
      (fields
        (field (name "NAME") "110Ω")
        (field (name "MANUFACTURER") "UNI-ROYAL(厚声)")
        (field (name "MANUFACTURER PART") "0603WAF1100T5E")
      )
      (libsource (lib "altium-import") (part "root_0_0603WAF1100T5E_"))
    )
    (comp (ref "R38")
      (value "110Ω")
      (description "电阻类型:厚膜电阻;阻值:110Ω;精度:±1%;功率:100mW;")
      (fields
        (field (name "NAME") "110Ω")
        (field (name "MANUFACTURER") "UNI-ROYAL(厚声)")
        (field (name "MANUFACTURER PART") "0603WAF1100T5E")
      )
      (libsource (lib "altium-import") (part "root_0_0603WAF1100T5E_"))
    )
    (comp (ref "R39")
      (value "110Ω")
      (description "电阻类型:厚膜电阻;阻值:110Ω;精度:±1%;功率:100mW;")
      (fields
        (field (name "NAME") "110Ω")
        (field (name "MANUFACTURER") "UNI-ROYAL(厚声)")
        (field (name "MANUFACTURER PART") "0603WAF1100T5E")
      )
      (libsource (lib "altium-import") (part "root_0_0603WAF1100T5E_"))
    )
    (comp (ref "R40")
      (value "110Ω")
      (description "电阻类型:厚膜电阻;阻值:110Ω;精度:±1%;功率:100mW;")
      (fields
        (field (name "NAME") "110Ω")
        (field (name "MANUFACTURER") "UNI-ROYAL(厚声)")
        (field (name "MANUFACTURER PART") "0603WAF1100T5E")
      )
      (libsource (lib "altium-import") (part "root_0_0603WAF1100T5E_"))
    )
    (comp (ref "R41")
      (value "110Ω")
      (description "电阻类型:厚膜电阻;阻值:110Ω;精度:±1%;功率:100mW;")
      (fields
        (field (name "NAME") "110Ω")
        (field (name "MANUFACTURER") "UNI-ROYAL(厚声)")
        (field (name "MANUFACTURER PART") "0603WAF1100T5E")
      )
      (libsource (lib "altium-import") (part "root_0_0603WAF1100T5E_"))
    )
    (comp (ref "R42")
      (value "110Ω")
      (description "电阻类型:厚膜电阻;阻值:110Ω;精度:±1%;功率:100mW;")
      (fields
        (field (name "NAME") "110Ω")
        (field (name "MANUFACTURER") "UNI-ROYAL(厚声)")
        (field (name "MANUFACTURER PART") "0603WAF1100T5E")
      )
      (libsource (lib "altium-import") (part "root_0_0603WAF1100T5E_"))
    )
    (comp (ref "R43")
      (value "110Ω")
      (description "电阻类型:厚膜电阻;阻值:110Ω;精度:±1%;功率:100mW;")
      (fields
        (field (name "NAME") "110Ω")
        (field (name "MANUFACTURER") "UNI-ROYAL(厚声)")
        (field (name "MANUFACTURER PART") "0603WAF1100T5E")
      )
      (libsource (lib "altium-import") (part "root_0_0603WAF1100T5E_"))
    )
    (comp (ref "R44")
      (value "110Ω")
      (description "电阻类型:厚膜电阻;阻值:110Ω;精度:±1%;功率:100mW;")
      (fields
        (field (name "NAME") "110Ω")
        (field (name "MANUFACTURER") "UNI-ROYAL(厚声)")
        (field (name "MANUFACTURER PART") "0603WAF1100T5E")
      )
      (libsource (lib "altium-import") (part "root_0_0603WAF1100T5E_"))
    )
    (comp (ref "R45")
      (value "110Ω")
      (description "电阻类型:厚膜电阻;阻值:110Ω;精度:±1%;功率:100mW;")
      (fields
        (field (name "NAME") "110Ω")
        (field (name "MANUFACTURER") "UNI-ROYAL(厚声)")
        (field (name "MANUFACTURER PART") "0603WAF1100T5E")
      )
      (libsource (lib "altium-import") (part "root_0_0603WAF1100T5E_"))
    )
    (comp (ref "R46")
      (value "110Ω")
      (description "电阻类型:厚膜电阻;阻值:110Ω;精度:±1%;功率:100mW;")
      (fields
        (field (name "NAME") "110Ω")
        (field (name "MANUFACTURER") "UNI-ROYAL(厚声)")
        (field (name "MANUFACTURER PART") "0603WAF1100T5E")
      )
      (libsource (lib "altium-import") (part "root_0_0603WAF1100T5E_"))
    )
    (comp (ref "R47")
      (value "110Ω")
      (description "电阻类型:厚膜电阻;阻值:110Ω;精度:±1%;功率:100mW;")
      (fields
        (field (name "NAME") "110Ω")
        (field (name "MANUFACTURER") "UNI-ROYAL(厚声)")
        (field (name "MANUFACTURER PART") "0603WAF1100T5E")
      )
      (libsource (lib "altium-import") (part "root_0_0603WAF1100T5E_"))
    )
    (comp (ref "R48")
      (value "110Ω")
      (description "电阻类型:厚膜电阻;阻值:110Ω;精度:±1%;功率:100mW;")
      (fields
        (field (name "NAME") "110Ω")
        (field (name "MANUFACTURER") "UNI-ROYAL(厚声)")
        (field (name "MANUFACTURER PART") "0603WAF1100T5E")
      )
      (libsource (lib "altium-import") (part "root_0_0603WAF1100T5E_"))
    )
    (comp (ref "U1")
      (value "74HC595D")
      (description "功能:串行至串行或并行;电源电压:2V~6V;")
      (fields (field (name "NAME") "74HC595D") (field (name "MANUFACTURER") "TOSHIBA(东芝)"))
      (libsource (lib "altium-import") (part "root_0_74HC595D_C431479_"))
    )
    (comp (ref "U2")
      (value "74HC595D")
      (description "功能:串行至串行或并行;电源电压:2V~6V;")
      (fields (field (name "NAME") "74HC595D") (field (name "MANUFACTURER") "TOSHIBA(东芝)"))
      (libsource (lib "altium-import") (part "root_0_74HC595D_C431479_"))
    )
    (comp (ref "U4")
      (value "排母1*8P")
      (description "排数:单排;总孔位数:8;间距:1.27mm;行距:-;安装类型:直插;塑高:-;触头材质:-;触头镀层:-;")
      (fields (field (name "NAME") "排母1*8P") (field (name "MANUFACTURER") "BOOMELE(博穆精密)"))
      (libsource (lib "altium-import") (part "root_0_mirrored_排母1*8P_"))
    )
  )
  (nets
    (net (code "1") (name "<NO NET>") (class "Default")
      (node (ref "C1") (pin "2") (pinfunction "2_2") (pintype "passive"))
      (node (ref "U1") (pin "13") (pinfunction "G#_13") (pintype "passive"))
      (node (ref "U1") (pin "8") (pinfunction "GND_8") (pintype "passive"))
      (node (ref "U2") (pin "13") (pinfunction "G#_13") (pintype "passive"))
      (node (ref "U2") (pin "8") (pinfunction "GND_8") (pintype "passive"))
      (node (ref "U4") (pin "8") (pinfunction "8_8") (pintype "passive"))
    )
    (net (code "2") (name "Net-(LED1-+)") (class "Default")
      (node (ref "LED1") (pin "1") (pinfunction "+_1") (pintype "passive"))
      (node (ref "R1") (pin "1") (pinfunction "1_1") (pintype "passive"))
    )
    (net (code "3") (name "Net-(LED1--)") (class "Default")
      (node (ref "LED1") (pin "2") (pinfunction "-_2") (pintype "passive"))
      (node (ref "LED2") (pin "2") (pinfunction "-_2") (pintype "passive"))
      (node (ref "LED3") (pin "2") (pinfunction "-_2") (pintype "passive"))
      (node (ref "LED4") (pin "2") (pinfunction "-_2") (pintype "passive"))
      (node (ref "LED5") (pin "2") (pinfunction "-_2") (pintype "passive"))
      (node (ref "LED6") (pin "2") (pinfunction "-_2") (pintype "passive"))
      (node (ref "LED7") (pin "2") (pinfunction "-_2") (pintype "passive"))
      (node (ref "LED8") (pin "2") (pinfunction "-_2") (pintype "passive"))
      (node (ref "U2") (pin "15") (pinfunction "QA_15") (pintype "passive"))
    )
    (net (code "4") (name "Net-(LED2-+)") (class "Default")
      (node (ref "LED2") (pin "1") (pinfunction "+_1") (pintype "passive"))
      (node (ref "R2") (pin "1") (pinfunction "1_1") (pintype "passive"))
    )
    (net (code "5") (name "Net-(LED3-+)") (class "Default")
      (node (ref "LED3") (pin "1") (pinfunction "+_1") (pintype "passive"))
      (node (ref "R3") (pin "1") (pinfunction "1_1") (pintype "passive"))
    )
    (net (code "6") (name "Net-(LED4-+)") (class "Default")
      (node (ref "LED4") (pin "1") (pinfunction "+_1") (pintype "passive"))
      (node (ref "R4") (pin "1") (pinfunction "1_1") (pintype "passive"))
    )
    (net (code "7") (name "Net-(LED5-+)") (class "Default")
      (node (ref "LED5") (pin "1") (pinfunction "+_1") (pintype "passive"))
      (node (ref "R5") (pin "1") (pinfunction "1_1") (pintype "passive"))
    )
    (net (code "8") (name "Net-(LED6-+)") (class "Default")
      (node (ref "LED6") (pin "1") (pinfunction "+_1") (pintype "passive"))
      (node (ref "R6") (pin "1") (pinfunction "1_1") (pintype "passive"))
    )
    (net (code "9") (name "Net-(LED7-+)") (class "Default")
      (node (ref "LED7") (pin "1") (pinfunction "+_1") (pintype "passive"))
      (node (ref "R7") (pin "1") (pinfunction "1_1") (pintype "passive"))
    )
    (net (code "10") (name "Net-(LED8-+)") (class "Default")
      (node (ref "LED8") (pin "1") (pinfunction "+_1") (pintype "passive"))
      (node (ref "R8") (pin "1") (pinfunction "1_1") (pintype "passive"))
    )
    (net (code "11") (name "Net-(LED9-+)") (class "Default")
      (node (ref "LED9") (pin "1") (pinfunction "+_1") (pintype "passive"))
      (node (ref "R9") (pin "1") (pinfunction "1_1") (pintype "passive"))
    )
    (net (code "12") (name "Net-(LED10-+)") (class "Default")
      (node (ref "LED10") (pin "1") (pinfunction "+_1") (pintype "passive"))
      (node (ref "R10") (pin "1") (pinfunction "1_1") (pintype "passive"))
    )
    (net (code "13") (name "Net-(LED10--)") (class "Default")
      (node (ref "LED10") (pin "2") (pinfunction "-_2") (pintype "passive"))
      (node (ref "LED11") (pin "2") (pinfunction "-_2") (pintype "passive"))
      (node (ref "LED12") (pin "2") (pinfunction "-_2") (pintype "passive"))
      (node (ref "LED13") (pin "2") (pinfunction "-_2") (pintype "passive"))
      (node (ref "LED14") (pin "2") (pinfunction "-_2") (pintype "passive"))
      (node (ref "LED15") (pin "2") (pinfunction "-_2") (pintype "passive"))
      (node (ref "LED16") (pin "2") (pinfunction "-_2") (pintype "passive"))
      (node (ref "LED9") (pin "2") (pinfunction "-_2") (pintype "passive"))
      (node (ref "U2") (pin "1") (pinfunction "QB_1") (pintype "passive"))
    )
    (net (code "14") (name "Net-(LED11-+)") (class "Default")
      (node (ref "LED11") (pin "1") (pinfunction "+_1") (pintype "passive"))
      (node (ref "R11") (pin "1") (pinfunction "1_1") (pintype "passive"))
    )
    (net (code "15") (name "Net-(LED12-+)") (class "Default")
      (node (ref "LED12") (pin "1") (pinfunction "+_1") (pintype "passive"))
      (node (ref "R12") (pin "1") (pinfunction "1_1") (pintype "passive"))
    )
    (net (code "16") (name "Net-(LED13-+)") (class "Default")
      (node (ref "LED13") (pin "1") (pinfunction "+_1") (pintype "passive"))
      (node (ref "R13") (pin "1") (pinfunction "1_1") (pintype "passive"))
    )
    (net (code "17") (name "Net-(LED14-+)") (class "Default")
      (node (ref "LED14") (pin "1") (pinfunction "+_1") (pintype "passive"))
      (node (ref "R14") (pin "1") (pinfunction "1_1") (pintype "passive"))
    )
    (net (code "18") (name "Net-(LED15-+)") (class "Default")
      (node (ref "LED15") (pin "1") (pinfunction "+_1") (pintype "passive"))
      (node (ref "R15") (pin "1") (pinfunction "1_1") (pintype "passive"))
    )
    (net (code "19") (name "Net-(LED16-+)") (class "Default")
      (node (ref "LED16") (pin "1") (pinfunction "+_1") (pintype "passive"))
      (node (ref "R16") (pin "1") (pinfunction "1_1") (pintype "passive"))
    )
    (net (code "20") (name "Net-(LED17-+)") (class "Default")
      (node (ref "LED17") (pin "1") (pinfunction "+_1") (pintype "passive"))
      (node (ref "R17") (pin "1") (pinfunction "1_1") (pintype "passive"))
    )
    (net (code "21") (name "Net-(LED17--)") (class "Default")
      (node (ref "LED17") (pin "2") (pinfunction "-_2") (pintype "passive"))
      (node (ref "LED18") (pin "2") (pinfunction "-_2") (pintype "passive"))
      (node (ref "LED19") (pin "2") (pinfunction "-_2") (pintype "passive"))
      (node (ref "LED20") (pin "2") (pinfunction "-_2") (pintype "passive"))
      (node (ref "LED21") (pin "2") (pinfunction "-_2") (pintype "passive"))
      (node (ref "LED22") (pin "2") (pinfunction "-_2") (pintype "passive"))
      (node (ref "LED23") (pin "2") (pinfunction "-_2") (pintype "passive"))
      (node (ref "LED24") (pin "2") (pinfunction "-_2") (pintype "passive"))
      (node (ref "U2") (pin "2") (pinfunction "QC_2") (pintype "passive"))
    )
    (net (code "22") (name "Net-(LED18-+)") (class "Default")
      (node (ref "LED18") (pin "1") (pinfunction "+_1") (pintype "passive"))
      (node (ref "R18") (pin "1") (pinfunction "1_1") (pintype "passive"))
    )
    (net (code "23") (name "Net-(LED19-+)") (class "Default")
      (node (ref "LED19") (pin "1") (pinfunction "+_1") (pintype "passive"))
      (node (ref "R19") (pin "1") (pinfunction "1_1") (pintype "passive"))
    )
    (net (code "24") (name "Net-(LED20-+)") (class "Default")
      (node (ref "LED20") (pin "1") (pinfunction "+_1") (pintype "passive"))
      (node (ref "R20") (pin "1") (pinfunction "1_1") (pintype "passive"))
    )
    (net (code "25") (name "Net-(LED21-+)") (class "Default")
      (node (ref "LED21") (pin "1") (pinfunction "+_1") (pintype "passive"))
      (node (ref "R21") (pin "1") (pinfunction "1_1") (pintype "passive"))
    )
    (net (code "26") (name "Net-(LED22-+)") (class "Default")
      (node (ref "LED22") (pin "1") (pinfunction "+_1") (pintype "passive"))
      (node (ref "R22") (pin "1") (pinfunction "1_1") (pintype "passive"))
    )
    (net (code "27") (name "Net-(LED23-+)") (class "Default")
      (node (ref "LED23") (pin "1") (pinfunction "+_1") (pintype "passive"))
      (node (ref "R23") (pin "1") (pinfunction "1_1") (pintype "passive"))
    )
    (net (code "28") (name "Net-(LED24-+)") (class "Default")
      (node (ref "LED24") (pin "1") (pinfunction "+_1") (pintype "passive"))
      (node (ref "R24") (pin "1") (pinfunction "1_1") (pintype "passive"))
    )
    (net (code "29") (name "Net-(LED25-+)") (class "Default")
      (node (ref "LED25") (pin "1") (pinfunction "+_1") (pintype "passive"))
      (node (ref "R25") (pin "1") (pinfunction "1_1") (pintype "passive"))
    )
    (net (code "30") (name "Net-(LED25--)") (class "Default")
      (node (ref "LED25") (pin "2") (pinfunction "-_2") (pintype "passive"))
      (node (ref "LED26") (pin "2") (pinfunction "-_2") (pintype "passive"))
      (node (ref "LED27") (pin "2") (pinfunction "-_2") (pintype "passive"))
      (node (ref "LED28") (pin "2") (pinfunction "-_2") (pintype "passive"))
      (node (ref "LED29") (pin "2") (pinfunction "-_2") (pintype "passive"))
      (node (ref "LED30") (pin "2") (pinfunction "-_2") (pintype "passive"))
      (node (ref "LED31") (pin "2") (pinfunction "-_2") (pintype "passive"))
      (node (ref "LED32") (pin "2") (pinfunction "-_2") (pintype "passive"))
      (node (ref "U2") (pin "3") (pinfunction "QD_3") (pintype "passive"))
    )
    (net (code "31") (name "Net-(LED26-+)") (class "Default")
      (node (ref "LED26") (pin "1") (pinfunction "+_1") (pintype "passive"))
      (node (ref "R26") (pin "1") (pinfunction "1_1") (pintype "passive"))
    )
    (net (code "32") (name "Net-(LED27-+)") (class "Default")
      (node (ref "LED27") (pin "1") (pinfunction "+_1") (pintype "passive"))
      (node (ref "R27") (pin "1") (pinfunction "1_1") (pintype "passive"))
    )
    (net (code "33") (name "Net-(LED28-+)") (class "Default")
      (node (ref "LED28") (pin "1") (pinfunction "+_1") (pintype "passive"))
      (node (ref "R28") (pin "1") (pinfunction "1_1") (pintype "passive"))
    )
    (net (code "34") (name "Net-(LED29-+)") (class "Default")
      (node (ref "LED29") (pin "1") (pinfunction "+_1") (pintype "passive"))
      (node (ref "R29") (pin "1") (pinfunction "1_1") (pintype "passive"))
    )
    (net (code "35") (name "Net-(LED30-+)") (class "Default")
      (node (ref "LED30") (pin "1") (pinfunction "+_1") (pintype "passive"))
      (node (ref "R30") (pin "1") (pinfunction "1_1") (pintype "passive"))
    )
    (net (code "36") (name "Net-(LED31-+)") (class "Default")
      (node (ref "LED31") (pin "1") (pinfunction "+_1") (pintype "passive"))
      (node (ref "R31") (pin "1") (pinfunction "1_1") (pintype "passive"))
    )
    (net (code "37") (name "Net-(LED32-+)") (class "Default")
      (node (ref "LED32") (pin "1") (pinfunction "+_1") (pintype "passive"))
      (node (ref "R32") (pin "1") (pinfunction "1_1") (pintype "passive"))
    )
    (net (code "38") (name "Net-(LED33-+)") (class "Default")
      (node (ref "LED33") (pin "1") (pinfunction "+_1") (pintype "passive"))
      (node (ref "R33") (pin "1") (pinfunction "1_1") (pintype "passive"))
    )
    (net (code "39") (name "Net-(LED33--)") (class "Default")
      (node (ref "LED33") (pin "2") (pinfunction "-_2") (pintype "passive"))
      (node (ref "LED34") (pin "2") (pinfunction "-_2") (pintype "passive"))
      (node (ref "LED35") (pin "2") (pinfunction "-_2") (pintype "passive"))
      (node (ref "LED36") (pin "2") (pinfunction "-_2") (pintype "passive"))
      (node (ref "LED37") (pin "2") (pinfunction "-_2") (pintype "passive"))
      (node (ref "LED38") (pin "2") (pinfunction "-_2") (pintype "passive"))
      (node (ref "LED39") (pin "2") (pinfunction "-_2") (pintype "passive"))
      (node (ref "LED40") (pin "2") (pinfunction "-_2") (pintype "passive"))
      (node (ref "U2") (pin "4") (pinfunction "QE_4") (pintype "passive"))
    )
    (net (code "40") (name "Net-(LED34-+)") (class "Default")
      (node (ref "LED34") (pin "1") (pinfunction "+_1") (pintype "passive"))
      (node (ref "R34") (pin "1") (pinfunction "1_1") (pintype "passive"))
    )
    (net (code "41") (name "Net-(LED35-+)") (class "Default")
      (node (ref "LED35") (pin "1") (pinfunction "+_1") (pintype "passive"))
      (node (ref "R35") (pin "1") (pinfunction "1_1") (pintype "passive"))
    )
    (net (code "42") (name "Net-(LED36-+)") (class "Default")
      (node (ref "LED36") (pin "1") (pinfunction "+_1") (pintype "passive"))
      (node (ref "R36") (pin "1") (pinfunction "1_1") (pintype "passive"))
    )
    (net (code "43") (name "Net-(LED37-+)") (class "Default")
      (node (ref "LED37") (pin "1") (pinfunction "+_1") (pintype "passive"))
      (node (ref "R37") (pin "1") (pinfunction "1_1") (pintype "passive"))
    )
    (net (code "44") (name "Net-(LED38-+)") (class "Default")
      (node (ref "LED38") (pin "1") (pinfunction "+_1") (pintype "passive"))
      (node (ref "R38") (pin "1") (pinfunction "1_1") (pintype "passive"))
    )
    (net (code "45") (name "Net-(LED39-+)") (class "Default")
      (node (ref "LED39") (pin "1") (pinfunction "+_1") (pintype "passive"))
      (node (ref "R39") (pin "1") (pinfunction "1_1") (pintype "passive"))
    )
    (net (code "46") (name "Net-(LED40-+)") (class "Default")
      (node (ref "LED40") (pin "1") (pinfunction "+_1") (pintype "passive"))
      (node (ref "R40") (pin "1") (pinfunction "1_1") (pintype "passive"))
    )
    (net (code "47") (name "Net-(LED41-+)") (class "Default")
      (node (ref "LED41") (pin "1") (pinfunction "+_1") (pintype "passive"))
      (node (ref "R41") (pin "1") (pinfunction "1_1") (pintype "passive"))
    )
    (net (code "48") (name "Net-(LED41--)") (class "Default")
      (node (ref "LED41") (pin "2") (pinfunction "-_2") (pintype "passive"))
      (node (ref "LED42") (pin "2") (pinfunction "-_2") (pintype "passive"))
      (node (ref "LED43") (pin "2") (pinfunction "-_2") (pintype "passive"))
      (node (ref "LED44") (pin "2") (pinfunction "-_2") (pintype "passive"))
      (node (ref "LED45") (pin "2") (pinfunction "-_2") (pintype "passive"))
      (node (ref "LED46") (pin "2") (pinfunction "-_2") (pintype "passive"))
      (node (ref "LED47") (pin "2") (pinfunction "-_2") (pintype "passive"))
      (node (ref "LED48") (pin "2") (pinfunction "-_2") (pintype "passive"))
      (node (ref "U2") (pin "5") (pinfunction "QF_5") (pintype "passive"))
    )
    (net (code "49") (name "Net-(LED42-+)") (class "Default")
      (node (ref "LED42") (pin "1") (pinfunction "+_1") (pintype "passive"))
      (node (ref "R42") (pin "1") (pinfunction "1_1") (pintype "passive"))
    )
    (net (code "50") (name "Net-(LED43-+)") (class "Default")
      (node (ref "LED43") (pin "1") (pinfunction "+_1") (pintype "passive"))
      (node (ref "R43") (pin "1") (pinfunction "1_1") (pintype "passive"))
    )
    (net (code "51") (name "Net-(LED44-+)") (class "Default")
      (node (ref "LED44") (pin "1") (pinfunction "+_1") (pintype "passive"))
      (node (ref "R44") (pin "1") (pinfunction "1_1") (pintype "passive"))
    )
    (net (code "52") (name "Net-(LED45-+)") (class "Default")
      (node (ref "LED45") (pin "1") (pinfunction "+_1") (pintype "passive"))
      (node (ref "R45") (pin "1") (pinfunction "1_1") (pintype "passive"))
    )
    (net (code "53") (name "Net-(LED46-+)") (class "Default")
      (node (ref "LED46") (pin "1") (pinfunction "+_1") (pintype "passive"))
      (node (ref "R46") (pin "1") (pinfunction "1_1") (pintype "passive"))
    )
    (net (code "54") (name "Net-(LED47-+)") (class "Default")
      (node (ref "LED47") (pin "1") (pinfunction "+_1") (pintype "passive"))
      (node (ref "R47") (pin "1") (pinfunction "1_1") (pintype "passive"))
    )
    (net (code "55") (name "Net-(LED48-+)") (class "Default")
      (node (ref "LED48") (pin "1") (pinfunction "+_1") (pintype "passive"))
      (node (ref "R48") (pin "1") (pinfunction "1_1") (pintype "passive"))
    )
    (net (code "56") (name "Net-(U1-QA)") (class "Default")
      (node (ref "R1") (pin "2") (pinfunction "2_2") (pintype "passive"))
      (node (ref "R17") (pin "2") (pinfunction "2_2") (pintype "passive"))
      (node (ref "R25") (pin "2") (pinfunction "2_2") (pintype "passive"))
      (node (ref "R33") (pin "2") (pinfunction "2_2") (pintype "passive"))
      (node (ref "R41") (pin "2") (pinfunction "2_2") (pintype "passive"))
      (node (ref "R9") (pin "2") (pinfunction "2_2") (pintype "passive"))
      (node (ref "U1") (pin "15") (pinfunction "QA_15") (pintype "passive"))
    )
    (net (code "57") (name "Net-(U1-QB)") (class "Default")
      (node (ref "R10") (pin "2") (pinfunction "2_2") (pintype "passive"))
      (node (ref "R18") (pin "2") (pinfunction "2_2") (pintype "passive"))
      (node (ref "R2") (pin "2") (pinfunction "2_2") (pintype "passive"))
      (node (ref "R26") (pin "2") (pinfunction "2_2") (pintype "passive"))
      (node (ref "R34") (pin "2") (pinfunction "2_2") (pintype "passive"))
      (node (ref "R42") (pin "2") (pinfunction "2_2") (pintype "passive"))
      (node (ref "U1") (pin "1") (pinfunction "QB_1") (pintype "passive"))
    )
    (net (code "58") (name "Net-(U1-QC)") (class "Default")
      (node (ref "R11") (pin "2") (pinfunction "2_2") (pintype "passive"))
      (node (ref "R19") (pin "2") (pinfunction "2_2") (pintype "passive"))
      (node (ref "R27") (pin "2") (pinfunction "2_2") (pintype "passive"))
      (node (ref "R3") (pin "2") (pinfunction "2_2") (pintype "passive"))
      (node (ref "R35") (pin "2") (pinfunction "2_2") (pintype "passive"))
      (node (ref "R43") (pin "2") (pinfunction "2_2") (pintype "passive"))
      (node (ref "U1") (pin "2") (pinfunction "QC_2") (pintype "passive"))
    )
    (net (code "59") (name "Net-(U1-QD)") (class "Default")
      (node (ref "R12") (pin "2") (pinfunction "2_2") (pintype "passive"))
      (node (ref "R20") (pin "2") (pinfunction "2_2") (pintype "passive"))
      (node (ref "R28") (pin "2") (pinfunction "2_2") (pintype "passive"))
      (node (ref "R36") (pin "2") (pinfunction "2_2") (pintype "passive"))
      (node (ref "R4") (pin "2") (pinfunction "2_2") (pintype "passive"))
      (node (ref "R44") (pin "2") (pinfunction "2_2") (pintype "passive"))
      (node (ref "U1") (pin "3") (pinfunction "QD_3") (pintype "passive"))
    )
    (net (code "60") (name "Net-(U1-QE)") (class "Default")
      (node (ref "R13") (pin "2") (pinfunction "2_2") (pintype "passive"))
      (node (ref "R21") (pin "2") (pinfunction "2_2") (pintype "passive"))
      (node (ref "R29") (pin "2") (pinfunction "2_2") (pintype "passive"))
      (node (ref "R37") (pin "2") (pinfunction "2_2") (pintype "passive"))
      (node (ref "R45") (pin "2") (pinfunction "2_2") (pintype "passive"))
      (node (ref "R5") (pin "2") (pinfunction "2_2") (pintype "passive"))
      (node (ref "U1") (pin "4") (pinfunction "QE_4") (pintype "passive"))
    )
    (net (code "61") (name "Net-(U1-QF)") (class "Default")
      (node (ref "R14") (pin "2") (pinfunction "2_2") (pintype "passive"))
      (node (ref "R22") (pin "2") (pinfunction "2_2") (pintype "passive"))
      (node (ref "R30") (pin "2") (pinfunction "2_2") (pintype "passive"))
      (node (ref "R38") (pin "2") (pinfunction "2_2") (pintype "passive"))
      (node (ref "R46") (pin "2") (pinfunction "2_2") (pintype "passive"))
      (node (ref "R6") (pin "2") (pinfunction "2_2") (pintype "passive"))
      (node (ref "U1") (pin "5") (pinfunction "QF_5") (pintype "passive"))
    )
    (net (code "62") (name "Net-(U1-QG)") (class "Default")
      (node (ref "R15") (pin "2") (pinfunction "2_2") (pintype "passive"))
      (node (ref "R23") (pin "2") (pinfunction "2_2") (pintype "passive"))
      (node (ref "R31") (pin "2") (pinfunction "2_2") (pintype "passive"))
      (node (ref "R39") (pin "2") (pinfunction "2_2") (pintype "passive"))
      (node (ref "R47") (pin "2") (pinfunction "2_2") (pintype "passive"))
      (node (ref "R7") (pin "2") (pinfunction "2_2") (pintype "passive"))
      (node (ref "U1") (pin "6") (pinfunction "QG_6") (pintype "passive"))
    )
    (net (code "63") (name "Net-(U1-QH)") (class "Default")
      (node (ref "R16") (pin "2") (pinfunction "2_2") (pintype "passive"))
      (node (ref "R24") (pin "2") (pinfunction "2_2") (pintype "passive"))
      (node (ref "R32") (pin "2") (pinfunction "2_2") (pintype "passive"))
      (node (ref "R40") (pin "2") (pinfunction "2_2") (pintype "passive"))
      (node (ref "R48") (pin "2") (pinfunction "2_2") (pintype "passive"))
      (node (ref "R8") (pin "2") (pinfunction "2_2") (pintype "passive"))
      (node (ref "U1") (pin "7") (pinfunction "QH_7") (pintype "passive"))
    )
    (net (code "64") (name "Net-(U1-RCK)") (class "Default")
      (node (ref "U1") (pin "12") (pinfunction "RCK_12") (pintype "passive"))
      (node (ref "U4") (pin "4") (pinfunction "4_4") (pintype "passive"))
    )
    (net (code "65") (name "Net-(U1-SCK)") (class "Default")
      (node (ref "U1") (pin "11") (pinfunction "SCK_11") (pintype "passive"))
      (node (ref "U4") (pin "3") (pinfunction "3_3") (pintype "passive"))
    )
    (net (code "66") (name "Net-(U1-SI)") (class "Default")
      (node (ref "U1") (pin "14") (pinfunction "SI_14") (pintype "passive"))
      (node (ref "U4") (pin "2") (pinfunction "2_2") (pintype "passive"))
    )
    (net (code "67") (name "Net-(U2-RCK)") (class "Default")
      (node (ref "U2") (pin "12") (pinfunction "RCK_12") (pintype "passive"))
      (node (ref "U4") (pin "7") (pinfunction "7_7") (pintype "passive"))
    )
    (net (code "68") (name "Net-(U2-SCK)") (class "Default")
      (node (ref "U2") (pin "11") (pinfunction "SCK_11") (pintype "passive"))
      (node (ref "U4") (pin "6") (pinfunction "6_6") (pintype "passive"))
    )
    (net (code "69") (name "Net-(U2-SI)") (class "Default")
      (node (ref "U2") (pin "14") (pinfunction "SI_14") (pintype "passive"))
      (node (ref "U4") (pin "5") (pinfunction "5_5") (pintype "passive"))
    )
    (net (code "70") (name "VCC") (class "Default")
      (node (ref "C1") (pin "1") (pinfunction "1_1") (pintype "passive"))
      (node (ref "U1") (pin "10") (pinfunction "SCLR#_10") (pintype "passive"))
      (node (ref "U1") (pin "16") (pinfunction "VCC_16") (pintype "passive"))
      (node (ref "U2") (pin "10") (pinfunction "SCLR#_10") (pintype "passive"))
      (node (ref "U2") (pin "16") (pinfunction "VCC_16") (pintype "passive"))
      (node (ref "U4") (pin "1") (pinfunction "1_1") (pintype "passive"))
    )
    (net (code "71") (name "unconnected-(LED1-Pad3)") (class "Default")
      (node (ref "LED1") (pin "3") (pinfunction "3_3") (pintype "passive"))
    )
    (net (code "72") (name "unconnected-(LED2-Pad3)") (class "Default")
      (node (ref "LED2") (pin "3") (pinfunction "3_3") (pintype "passive"))
    )
    (net (code "73") (name "unconnected-(LED3-Pad3)") (class "Default")
      (node (ref "LED3") (pin "3") (pinfunction "3_3") (pintype "passive"))
    )
    (net (code "74") (name "unconnected-(LED4-Pad3)") (class "Default")
      (node (ref "LED4") (pin "3") (pinfunction "3_3") (pintype "passive"))
    )
    (net (code "75") (name "unconnected-(LED5-Pad3)") (class "Default")
      (node (ref "LED5") (pin "3") (pinfunction "3_3") (pintype "passive"))
    )
    (net (code "76") (name "unconnected-(LED6-Pad3)") (class "Default")
      (node (ref "LED6") (pin "3") (pinfunction "3_3") (pintype "passive"))
    )
    (net (code "77") (name "unconnected-(LED7-Pad3)") (class "Default")
      (node (ref "LED7") (pin "3") (pinfunction "3_3") (pintype "passive"))
    )
    (net (code "78") (name "unconnected-(LED8-Pad3)") (class "Default")
      (node (ref "LED8") (pin "3") (pinfunction "3_3") (pintype "passive"))
    )
    (net (code "79") (name "unconnected-(LED9-Pad3)") (class "Default")
      (node (ref "LED9") (pin "3") (pinfunction "3_3") (pintype "passive"))
    )
    (net (code "80") (name "unconnected-(LED10-Pad3)") (class "Default")
      (node (ref "LED10") (pin "3") (pinfunction "3_3") (pintype "passive"))
    )
    (net (code "81") (name "unconnected-(LED11-Pad3)") (class "Default")
      (node (ref "LED11") (pin "3") (pinfunction "3_3") (pintype "passive"))
    )
    (net (code "82") (name "unconnected-(LED12-Pad3)") (class "Default")
      (node (ref "LED12") (pin "3") (pinfunction "3_3") (pintype "passive"))
    )
    (net (code "83") (name "unconnected-(LED13-Pad3)") (class "Default")
      (node (ref "LED13") (pin "3") (pinfunction "3_3") (pintype "passive"))
    )
    (net (code "84") (name "unconnected-(LED14-Pad3)") (class "Default")
      (node (ref "LED14") (pin "3") (pinfunction "3_3") (pintype "passive"))
    )
    (net (code "85") (name "unconnected-(LED15-Pad3)") (class "Default")
      (node (ref "LED15") (pin "3") (pinfunction "3_3") (pintype "passive"))
    )
    (net (code "86") (name "unconnected-(LED16-Pad3)") (class "Default")
      (node (ref "LED16") (pin "3") (pinfunction "3_3") (pintype "passive"))
    )
    (net (code "87") (name "unconnected-(LED17-Pad3)") (class "Default")
      (node (ref "LED17") (pin "3") (pinfunction "3_3") (pintype "passive"))
    )
    (net (code "88") (name "unconnected-(LED18-Pad3)") (class "Default")
      (node (ref "LED18") (pin "3") (pinfunction "3_3") (pintype "passive"))
    )
    (net (code "89") (name "unconnected-(LED19-Pad3)") (class "Default")
      (node (ref "LED19") (pin "3") (pinfunction "3_3") (pintype "passive"))
    )
    (net (code "90") (name "unconnected-(LED20-Pad3)") (class "Default")
      (node (ref "LED20") (pin "3") (pinfunction "3_3") (pintype "passive"))
    )
    (net (code "91") (name "unconnected-(LED21-Pad3)") (class "Default")
      (node (ref "LED21") (pin "3") (pinfunction "3_3") (pintype "passive"))
    )
    (net (code "92") (name "unconnected-(LED22-Pad3)") (class "Default")
      (node (ref "LED22") (pin "3") (pinfunction "3_3") (pintype "passive"))
    )
    (net (code "93") (name "unconnected-(LED23-Pad3)") (class "Default")
      (node (ref "LED23") (pin "3") (pinfunction "3_3") (pintype "passive"))
    )
    (net (code "94") (name "unconnected-(LED24-Pad3)") (class "Default")
      (node (ref "LED24") (pin "3") (pinfunction "3_3") (pintype "passive"))
    )
    (net (code "95") (name "unconnected-(LED25-Pad3)") (class "Default")
      (node (ref "LED25") (pin "3") (pinfunction "3_3") (pintype "passive"))
    )
    (net (code "96") (name "unconnected-(LED26-Pad3)") (class "Default")
      (node (ref "LED26") (pin "3") (pinfunction "3_3") (pintype "passive"))
    )
    (net (code "97") (name "unconnected-(LED27-Pad3)") (class "Default")
      (node (ref "LED27") (pin "3") (pinfunction "3_3") (pintype "passive"))
    )
    (net (code "98") (name "unconnected-(LED28-Pad3)") (class "Default")
      (node (ref "LED28") (pin "3") (pinfunction "3_3") (pintype "passive"))
    )
    (net (code "99") (name "unconnected-(LED29-Pad3)") (class "Default")
      (node (ref "LED29") (pin "3") (pinfunction "3_3") (pintype "passive"))
    )
    (net (code "100") (name "unconnected-(LED30-Pad3)") (class "Default")
      (node (ref "LED30") (pin "3") (pinfunction "3_3") (pintype "passive"))
    )
    (net (code "101") (name "unconnected-(LED31-Pad3)") (class "Default")
      (node (ref "LED31") (pin "3") (pinfunction "3_3") (pintype "passive"))
    )
    (net (code "102") (name "unconnected-(LED32-Pad3)") (class "Default")
      (node (ref "LED32") (pin "3") (pinfunction "3_3") (pintype "passive"))
    )
    (net (code "103") (name "unconnected-(LED33-Pad3)") (class "Default")
      (node (ref "LED33") (pin "3") (pinfunction "3_3") (pintype "passive"))
    )
    (net (code "104") (name "unconnected-(LED34-Pad3)") (class "Default")
      (node (ref "LED34") (pin "3") (pinfunction "3_3") (pintype "passive"))
    )
    (net (code "105") (name "unconnected-(LED35-Pad3)") (class "Default")
      (node (ref "LED35") (pin "3") (pinfunction "3_3") (pintype "passive"))
    )
    (net (code "106") (name "unconnected-(LED36-Pad3)") (class "Default")
      (node (ref "LED36") (pin "3") (pinfunction "3_3") (pintype "passive"))
    )
    (net (code "107") (name "unconnected-(LED37-Pad3)") (class "Default")
      (node (ref "LED37") (pin "3") (pinfunction "3_3") (pintype "passive"))
    )
    (net (code "108") (name "unconnected-(LED38-Pad3)") (class "Default")
      (node (ref "LED38") (pin "3") (pinfunction "3_3") (pintype "passive"))
    )
    (net (code "109") (name "unconnected-(LED39-Pad3)") (class "Default")
      (node (ref "LED39") (pin "3") (pinfunction "3_3") (pintype "passive"))
    )
    (net (code "110") (name "unconnected-(LED40-Pad3)") (class "Default")
      (node (ref "LED40") (pin "3") (pinfunction "3_3") (pintype "passive"))
    )
    (net (code "111") (name "unconnected-(LED41-Pad3)") (class "Default")
      (node (ref "LED41") (pin "3") (pinfunction "3_3") (pintype "passive"))
    )
    (net (code "112") (name "unconnected-(LED42-Pad3)") (class "Default")
      (node (ref "LED42") (pin "3") (pinfunction "3_3") (pintype "passive"))
    )
    (net (code "113") (name "unconnected-(LED43-Pad3)") (class "Default")
      (node (ref "LED43") (pin "3") (pinfunction "3_3") (pintype "passive"))
    )
    (net (code "114") (name "unconnected-(LED44-Pad3)") (class "Default")
      (node (ref "LED44") (pin "3") (pinfunction "3_3") (pintype "passive"))
    )
    (net (code "115") (name "unconnected-(LED45-Pad3)") (class "Default")
      (node (ref "LED45") (pin "3") (pinfunction "3_3") (pintype "passive"))
    )
    (net (code "116") (name "unconnected-(LED46-Pad3)") (class "Default")
      (node (ref "LED46") (pin "3") (pinfunction "3_3") (pintype "passive"))
    )
    (net (code "117") (name "unconnected-(LED47-Pad3)") (class "Default")
      (node (ref "LED47") (pin "3") (pinfunction "3_3") (pintype "passive"))
    )
    (net (code "118") (name "unconnected-(LED48-Pad3)") (class "Default")
      (node (ref "LED48") (pin "3") (pinfunction "3_3") (pintype "passive"))
    )
    (net (code "119") (name "unconnected-(U1-QH&apos;-Pad9)") (class "Default")
      (node (ref "U1") (pin "9") (pinfunction "QH&apos;_9") (pintype "passive"))
    )
    (net (code "120") (name "unconnected-(U2-QG-Pad6)") (class "Default")
      (node (ref "U2") (pin "6") (pinfunction "QG_6") (pintype "passive"))
    )
    (net (code "121") (name "unconnected-(U2-QH&apos;-Pad9)") (class "Default")
      (node (ref "U2") (pin "9") (pinfunction "QH&apos;_9") (pintype "passive"))
    )
    (net (code "122") (name "unconnected-(U2-QH-Pad7)") (class "Default")
      (node (ref "U2") (pin "7") (pinfunction "QH_7") (pintype "passive"))
    )
  )
)
